# Swbot_shield.net
KiCad netlist of a schematic drawn in EAGLE
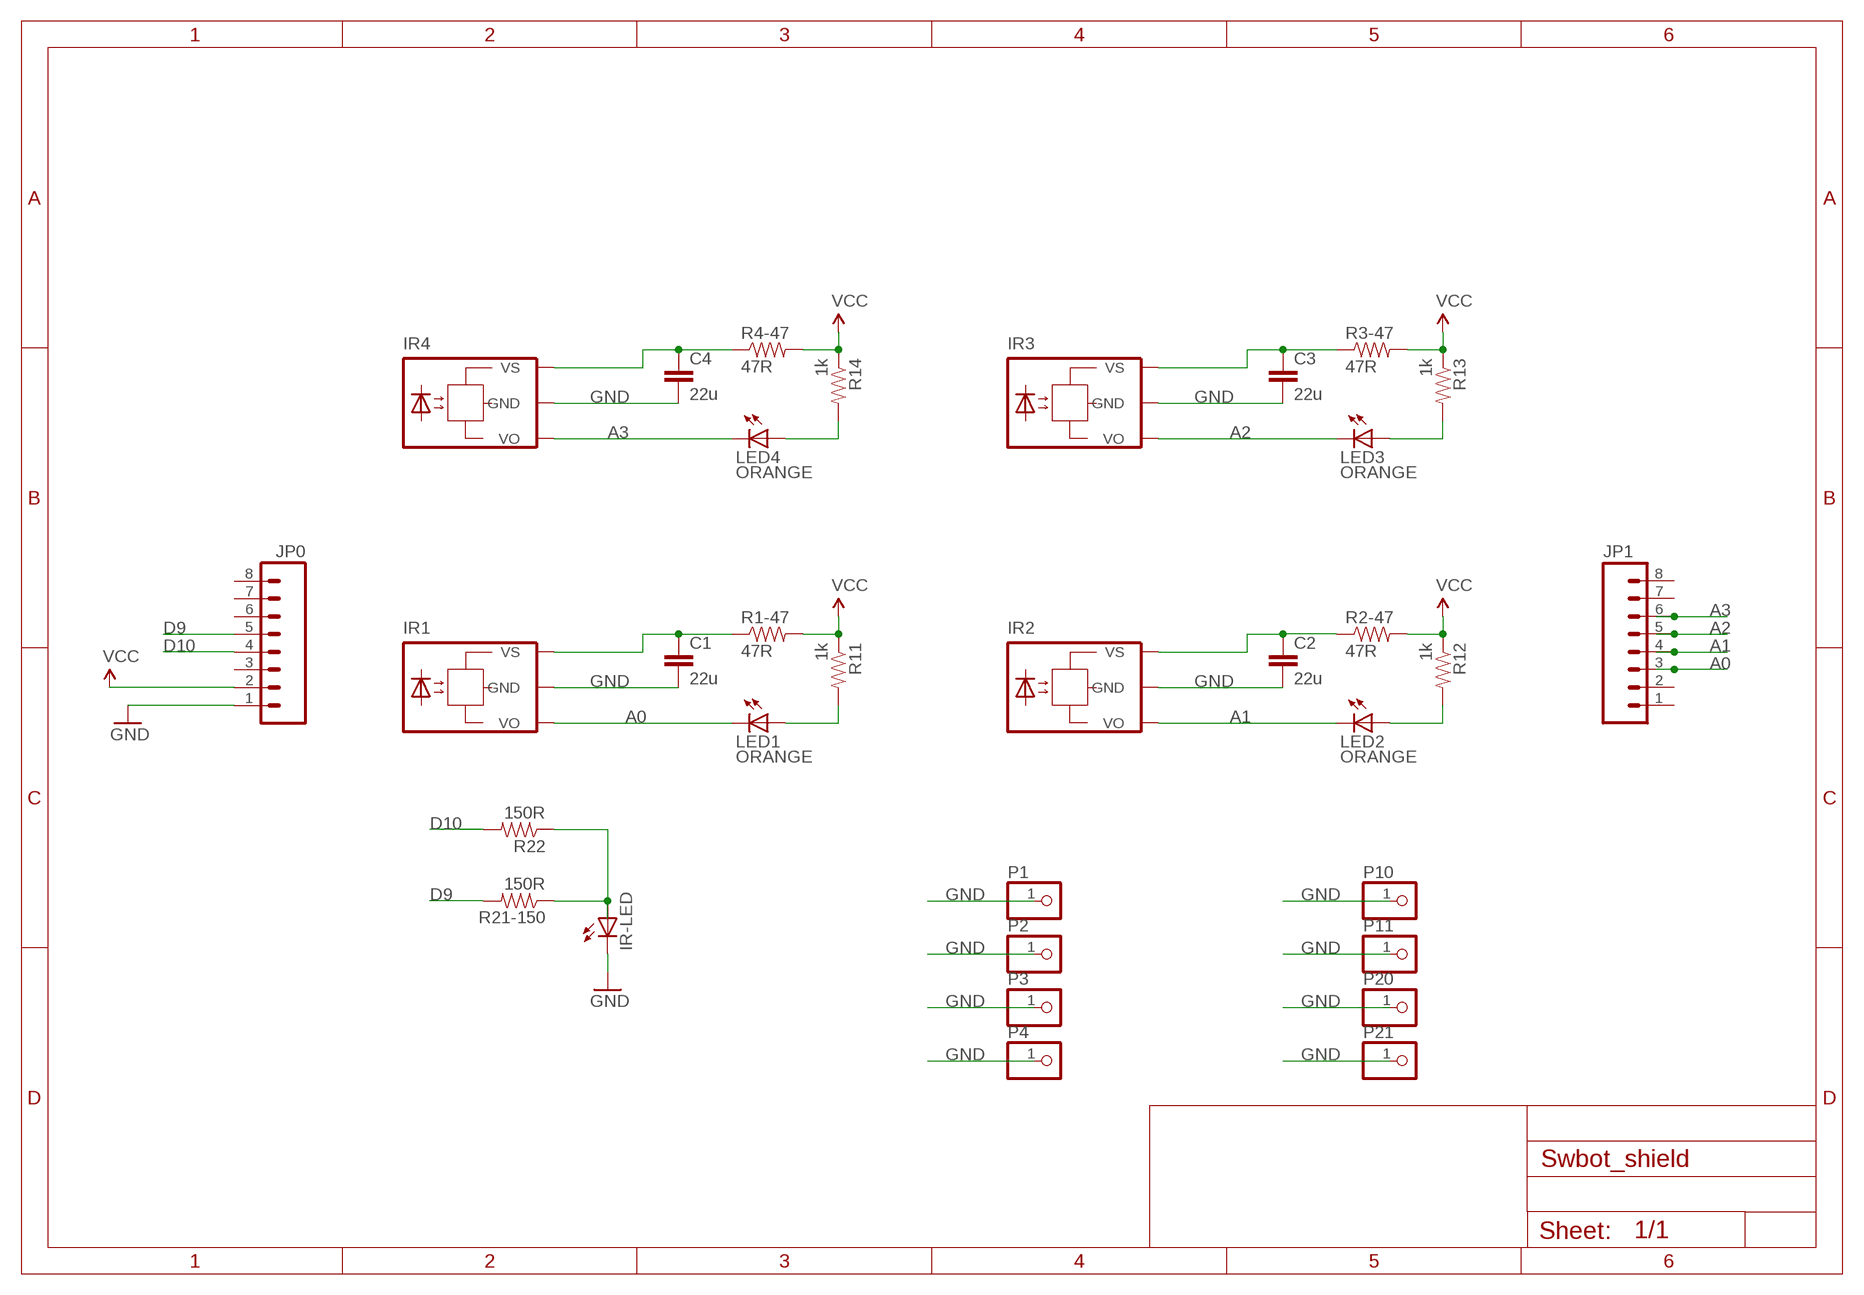
[diagram p0: schematic, sheet 1]

(export (version "E")
  (design (tool "Eeschema 10.0.6"))
  (components
    (comp (ref "C1")
      (value "22u")
      (footprint "eagle-import:1206")
      (libsource (lib "eagle-import") (part "CAP1206"))
    )
    (comp (ref "C2")
      (value "22u")
      (footprint "eagle-import:1206")
      (libsource (lib "eagle-import") (part "CAP1206"))
    )
    (comp (ref "C3")
      (value "22u")
      (footprint "eagle-import:1206")
      (libsource (lib "eagle-import") (part "CAP1206"))
    )
    (comp (ref "C4")
      (value "22u")
      (footprint "eagle-import:1206")
      (libsource (lib "eagle-import") (part "CAP1206"))
    )
    (comp (ref "IR-LED")
      (value "LED5MM")
      (footprint "eagle-import:LED5MM")
      (libsource (lib "eagle-import") (part "LED5MM"))
    )
    (comp (ref "IR1")
      (value "-NJL")
      (footprint "eagle-import:TSOP")
      (libsource (lib "eagle-import") (part "?-NJL"))
    )
    (comp (ref "IR2")
      (value "-NJL")
      (footprint "eagle-import:TSOP")
      (libsource (lib "eagle-import") (part "?-NJL"))
    )
    (comp (ref "IR3")
      (value "-NJL")
      (footprint "eagle-import:TSOP")
      (libsource (lib "eagle-import") (part "?-NJL"))
    )
    (comp (ref "IR4")
      (value "-NJL")
      (footprint "eagle-import:TSOP")
      (libsource (lib "eagle-import") (part "?-NJL"))
    )
    (comp (ref "JP0")
      (value "M08LOCK")
      (footprint "eagle-import:1X08_LOCK")
      (libsource (lib "eagle-import") (part "M08LOCK"))
    )
    (comp (ref "JP1")
      (value "M08LOCK")
      (footprint "eagle-import:1X08_LOCK")
      (libsource (lib "eagle-import") (part "M08LOCK"))
    )
    (comp (ref "LED1")
      (value "ORANGE")
      (footprint "eagle-import:CHIPLED_0805")
      (libsource (lib "eagle-import") (part "LEDCHIPLED_0805"))
    )
    (comp (ref "LED2")
      (value "ORANGE")
      (footprint "eagle-import:CHIPLED_0805")
      (libsource (lib "eagle-import") (part "LEDCHIPLED_0805"))
    )
    (comp (ref "LED3")
      (value "ORANGE")
      (footprint "eagle-import:CHIPLED_0805")
      (libsource (lib "eagle-import") (part "LEDCHIPLED_0805"))
    )
    (comp (ref "LED4")
      (value "ORANGE")
      (footprint "eagle-import:CHIPLED_0805")
      (libsource (lib "eagle-import") (part "LEDCHIPLED_0805"))
    )
    (comp (ref "P1")
      (value "PINHD-1X1")
      (footprint "eagle-import:1X01")
      (libsource (lib "eagle-import") (part "PINHD-1X1"))
    )
    (comp (ref "P2")
      (value "PINHD-1X1")
      (footprint "eagle-import:1X01")
      (libsource (lib "eagle-import") (part "PINHD-1X1"))
    )
    (comp (ref "P3")
      (value "PINHD-1X1")
      (footprint "eagle-import:1X01")
      (libsource (lib "eagle-import") (part "PINHD-1X1"))
    )
    (comp (ref "P4")
      (value "PINHD-1X1")
      (footprint "eagle-import:1X01")
      (libsource (lib "eagle-import") (part "PINHD-1X1"))
    )
    (comp (ref "P10")
      (value "PINHD-1X1")
      (footprint "eagle-import:1X01")
      (libsource (lib "eagle-import") (part "PINHD-1X1"))
    )
    (comp (ref "P11")
      (value "PINHD-1X1")
      (footprint "eagle-import:1X01")
      (libsource (lib "eagle-import") (part "PINHD-1X1"))
    )
    (comp (ref "P20")
      (value "PINHD-1X1")
      (footprint "eagle-import:1X01")
      (libsource (lib "eagle-import") (part "PINHD-1X1"))
    )
    (comp (ref "P21")
      (value "PINHD-1X1")
      (footprint "eagle-import:1X01")
      (libsource (lib "eagle-import") (part "PINHD-1X1"))
    )
    (comp (ref "R1-47")
      (value "47R")
      (footprint "eagle-import:0805")
      (libsource (lib "eagle-import") (part "RESISTOR0805-RES"))
    )
    (comp (ref "R2-47")
      (value "47R")
      (footprint "eagle-import:0805")
      (libsource (lib "eagle-import") (part "RESISTOR0805-RES"))
    )
    (comp (ref "R3-47")
      (value "47R")
      (footprint "eagle-import:0805")
      (libsource (lib "eagle-import") (part "RESISTOR0805-RES"))
    )
    (comp (ref "R4-47")
      (value "47R")
      (footprint "eagle-import:0805")
      (libsource (lib "eagle-import") (part "RESISTOR0805-RES"))
    )
    (comp (ref "R11")
      (value "1k")
      (footprint "eagle-import:0805")
      (libsource (lib "eagle-import") (part "RESISTOR0805-RES"))
    )
    (comp (ref "R12")
      (value "1k")
      (footprint "eagle-import:0805")
      (libsource (lib "eagle-import") (part "RESISTOR0805-RES"))
    )
    (comp (ref "R13")
      (value "1k")
      (footprint "eagle-import:0805")
      (libsource (lib "eagle-import") (part "RESISTOR0805-RES"))
    )
    (comp (ref "R14")
      (value "1k")
      (footprint "eagle-import:0805")
      (libsource (lib "eagle-import") (part "RESISTOR0805-RES"))
    )
    (comp (ref "R21-150")
      (value "150R")
      (footprint "eagle-import:0805")
      (libsource (lib "eagle-import") (part "RESISTOR0805-RES"))
    )
    (comp (ref "R22")
      (value "150R")
      (footprint "eagle-import:0805")
      (libsource (lib "eagle-import") (part "RESISTOR0805-RES"))
    )
  )
  (nets
    (net (code "1") (name "/A0") (class "Default")
      (node (ref "IR1") (pin "VO") (pinfunction "VO_VO") (pintype "output"))
      (node (ref "JP1") (pin "3") (pinfunction "3_3") (pintype "passive"))
      (node (ref "LED1") (pin "C") (pinfunction "C_C") (pintype "passive"))
    )
    (net (code "2") (name "/A1") (class "Default")
      (node (ref "IR2") (pin "VO") (pinfunction "VO_VO") (pintype "output"))
      (node (ref "JP1") (pin "4") (pinfunction "4_4") (pintype "passive"))
      (node (ref "LED2") (pin "C") (pinfunction "C_C") (pintype "passive"))
    )
    (net (code "3") (name "/A2") (class "Default")
      (node (ref "IR3") (pin "VO") (pinfunction "VO_VO") (pintype "output"))
      (node (ref "JP1") (pin "5") (pinfunction "5_5") (pintype "passive"))
      (node (ref "LED3") (pin "C") (pinfunction "C_C") (pintype "passive"))
    )
    (net (code "4") (name "/A3") (class "Default")
      (node (ref "IR4") (pin "VO") (pinfunction "VO_VO") (pintype "output"))
      (node (ref "JP1") (pin "6") (pinfunction "6_6") (pintype "passive"))
      (node (ref "LED4") (pin "C") (pinfunction "C_C") (pintype "passive"))
    )
    (net (code "5") (name "/D9") (class "Default")
      (node (ref "JP0") (pin "5") (pinfunction "5_5") (pintype "passive"))
      (node (ref "R21-150") (pin "2") (pinfunction "2_2") (pintype "passive"))
    )
    (net (code "6") (name "/D10") (class "Default")
      (node (ref "JP0") (pin "4") (pinfunction "4_4") (pintype "passive"))
      (node (ref "R22") (pin "2") (pinfunction "2_2") (pintype "passive"))
    )
    (net (code "7") (name "GND") (class "Default")
      (node (ref "C1") (pin "2") (pinfunction "2_2") (pintype "passive"))
      (node (ref "C2") (pin "2") (pinfunction "2_2") (pintype "passive"))
      (node (ref "C3") (pin "2") (pinfunction "2_2") (pintype "passive"))
      (node (ref "C4") (pin "2") (pinfunction "2_2") (pintype "passive"))
      (node (ref "IR-LED") (pin "K") (pinfunction "C_K") (pintype "passive"))
      (node (ref "IR1") (pin "GND") (pinfunction "GND_GND") (pintype "power_in"))
      (node (ref "IR2") (pin "GND") (pinfunction "GND_GND") (pintype "power_in"))
      (node (ref "IR3") (pin "GND") (pinfunction "GND_GND") (pintype "power_in"))
      (node (ref "IR4") (pin "GND") (pinfunction "GND_GND") (pintype "power_in"))
      (node (ref "JP0") (pin "1") (pinfunction "1_1") (pintype "passive"))
      (node (ref "P1") (pin "1") (pinfunction "1_1") (pintype "passive"))
      (node (ref "P10") (pin "1") (pinfunction "1_1") (pintype "passive"))
      (node (ref "P11") (pin "1") (pinfunction "1_1") (pintype "passive"))
      (node (ref "P2") (pin "1") (pinfunction "1_1") (pintype "passive"))
      (node (ref "P20") (pin "1") (pinfunction "1_1") (pintype "passive"))
      (node (ref "P21") (pin "1") (pinfunction "1_1") (pintype "passive"))
      (node (ref "P3") (pin "1") (pinfunction "1_1") (pintype "passive"))
      (node (ref "P4") (pin "1") (pinfunction "1_1") (pintype "passive"))
    )
    (net (code "8") (name "Net-(IR-LED-PadA)") (class "Default")
      (node (ref "IR-LED") (pin "A") (pinfunction "A_A") (pintype "passive"))
      (node (ref "R21-150") (pin "1") (pinfunction "1_1") (pintype "passive"))
      (node (ref "R22") (pin "1") (pinfunction "1_1") (pintype "passive"))
    )
    (net (code "9") (name "Net-(IR1-VS)") (class "Default")
      (node (ref "C1") (pin "1") (pinfunction "1_1") (pintype "passive"))
      (node (ref "IR1") (pin "VCC") (pinfunction "VS_VCC") (pintype "power_in"))
      (node (ref "R1-47") (pin "1") (pinfunction "1_1") (pintype "passive"))
    )
    (net (code "10") (name "Net-(IR2-VS)") (class "Default")
      (node (ref "C2") (pin "1") (pinfunction "1_1") (pintype "passive"))
      (node (ref "IR2") (pin "VCC") (pinfunction "VS_VCC") (pintype "power_in"))
      (node (ref "R2-47") (pin "1") (pinfunction "1_1") (pintype "passive"))
    )
    (net (code "11") (name "Net-(IR3-VS)") (class "Default")
      (node (ref "C3") (pin "1") (pinfunction "1_1") (pintype "passive"))
      (node (ref "IR3") (pin "VCC") (pinfunction "VS_VCC") (pintype "power_in"))
      (node (ref "R3-47") (pin "1") (pinfunction "1_1") (pintype "passive"))
    )
    (net (code "12") (name "Net-(IR4-VS)") (class "Default")
      (node (ref "C4") (pin "1") (pinfunction "1_1") (pintype "passive"))
      (node (ref "IR4") (pin "VCC") (pinfunction "VS_VCC") (pintype "power_in"))
      (node (ref "R4-47") (pin "1") (pinfunction "1_1") (pintype "passive"))
    )
    (net (code "13") (name "Net-(LED1-PadA)") (class "Default")
      (node (ref "LED1") (pin "A") (pinfunction "A_A") (pintype "passive"))
      (node (ref "R11") (pin "2") (pinfunction "2_2") (pintype "passive"))
    )
    (net (code "14") (name "Net-(LED2-PadA)") (class "Default")
      (node (ref "LED2") (pin "A") (pinfunction "A_A") (pintype "passive"))
      (node (ref "R12") (pin "2") (pinfunction "2_2") (pintype "passive"))
    )
    (net (code "15") (name "Net-(LED3-PadA)") (class "Default")
      (node (ref "LED3") (pin "A") (pinfunction "A_A") (pintype "passive"))
      (node (ref "R13") (pin "2") (pinfunction "2_2") (pintype "passive"))
    )
    (net (code "16") (name "Net-(LED4-PadA)") (class "Default")
      (node (ref "LED4") (pin "A") (pinfunction "A_A") (pintype "passive"))
      (node (ref "R14") (pin "2") (pinfunction "2_2") (pintype "passive"))
    )
    (net (code "17") (name "VCC") (class "Default")
      (node (ref "JP0") (pin "2") (pinfunction "2_2") (pintype "passive"))
      (node (ref "R1-47") (pin "2") (pinfunction "2_2") (pintype "passive"))
      (node (ref "R11") (pin "1") (pinfunction "1_1") (pintype "passive"))
      (node (ref "R12") (pin "1") (pinfunction "1_1") (pintype "passive"))
      (node (ref "R13") (pin "1") (pinfunction "1_1") (pintype "passive"))
      (node (ref "R14") (pin "1") (pinfunction "1_1") (pintype "passive"))
      (node (ref "R2-47") (pin "2") (pinfunction "2_2") (pintype "passive"))
      (node (ref "R3-47") (pin "2") (pinfunction "2_2") (pintype "passive"))
      (node (ref "R4-47") (pin "2") (pinfunction "2_2") (pintype "passive"))
    )
    (net (code "18") (name "unconnected-(JP0-Pad3)") (class "Default")
      (node (ref "JP0") (pin "3") (pinfunction "3_3") (pintype "passive"))
    )
    (net (code "19") (name "unconnected-(JP0-Pad6)") (class "Default")
      (node (ref "JP0") (pin "6") (pinfunction "6_6") (pintype "passive"))
    )
    (net (code "20") (name "unconnected-(JP0-Pad7)") (class "Default")
      (node (ref "JP0") (pin "7") (pinfunction "7_7") (pintype "passive"))
    )
    (net (code "21") (name "unconnected-(JP0-Pad8)") (class "Default")
      (node (ref "JP0") (pin "8") (pinfunction "8_8") (pintype "passive"))
    )
    (net (code "22") (name "unconnected-(JP1-Pad1)") (class "Default")
      (node (ref "JP1") (pin "1") (pinfunction "1_1") (pintype "passive"))
    )
    (net (code "23") (name "unconnected-(JP1-Pad2)") (class "Default")
      (node (ref "JP1") (pin "2") (pinfunction "2_2") (pintype "passive"))
    )
    (net (code "24") (name "unconnected-(JP1-Pad7)") (class "Default")
      (node (ref "JP1") (pin "7") (pinfunction "7_7") (pintype "passive"))
    )
    (net (code "25") (name "unconnected-(JP1-Pad8)") (class "Default")
      (node (ref "JP1") (pin "8") (pinfunction "8_8") (pintype "passive"))
    )
  )
)
